# MainBoard.net
KiCad netlist of a schematic drawn in Altium Designer
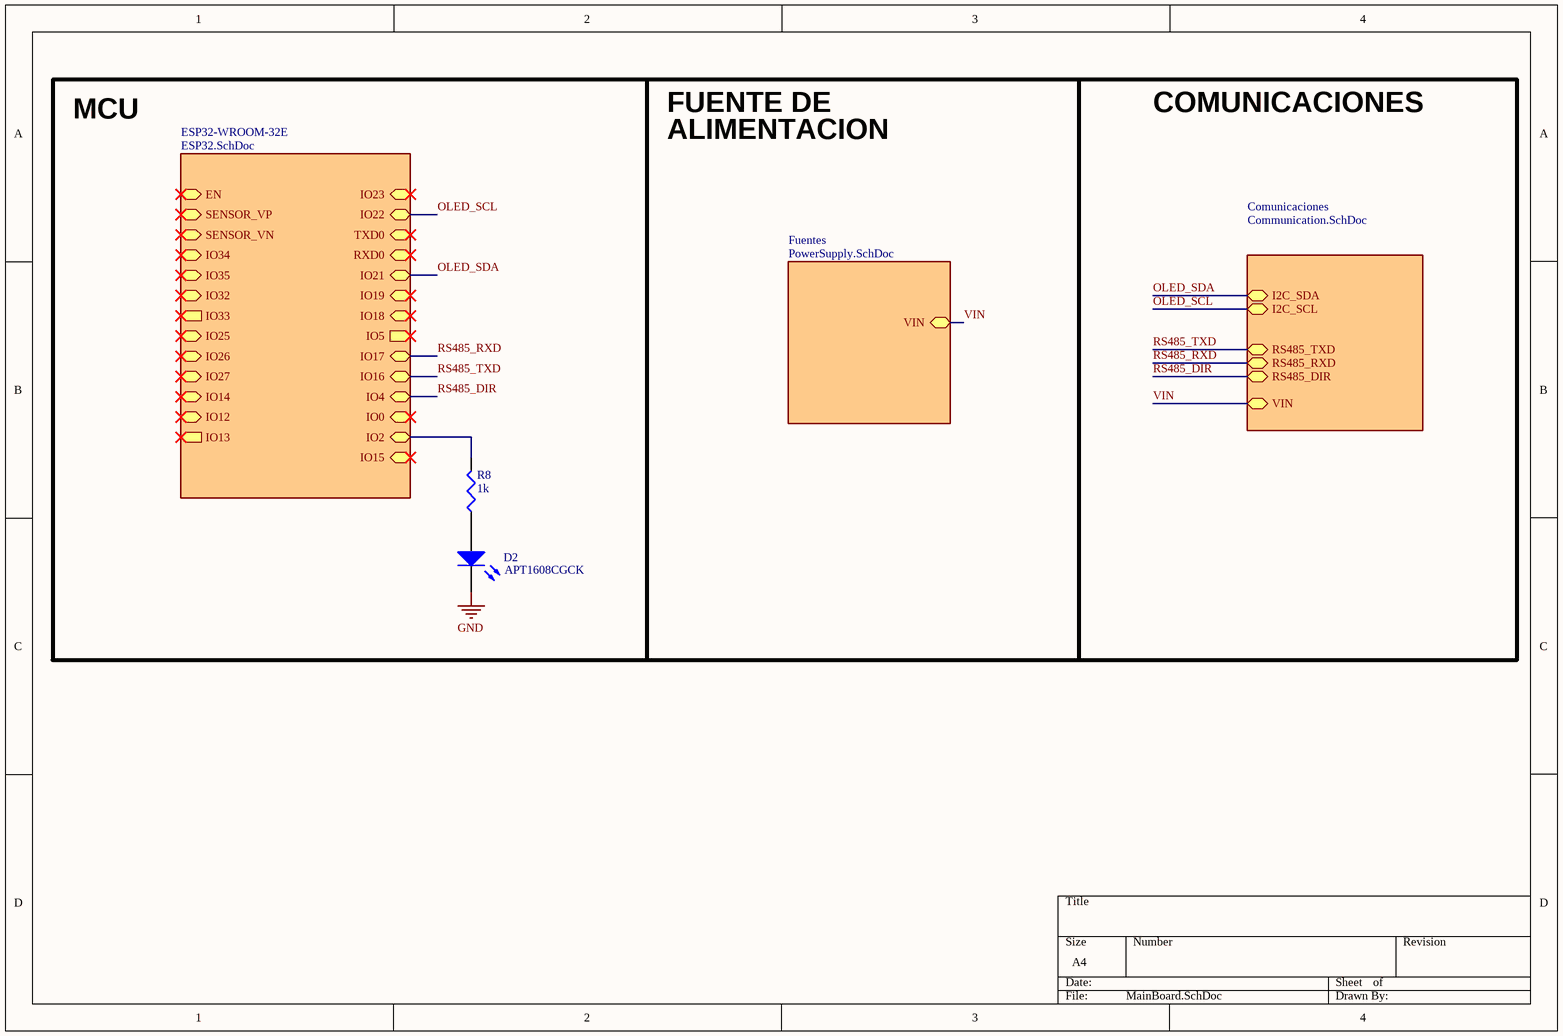
[diagram p0: MainBoard.SchDoc]

(export (version "E")
  (design (tool "Eeschema 10.0.6"))
  (components
    (comp (ref "D2")
      (value "APT1608CGCK")
      (footprint "ChipDiode1608")
      (description "LED 1.6x0.8 mm 570 nm GRN CLR SMD")
      (fields (field (name "PUBLISHER") "Altium Limited"))
      (libsource (lib "Miscellaneous Devices") (part "LED2"))
    )
    (comp (ref "R8")
      (value "1k")
      (footprint "RESC2012N")
      (description "Resistor")
      (fields (field (name "PUBLISHER") "Altium Limited"))
      (libsource (lib "Miscellaneous Devices") (part "Res3"))
    )
  )
  (nets
    (net (code "3") (name "/IO2") (class "Default")
      (node (ref "R8") (pin "2") (pinfunction "2_2") (pintype "passive"))
    )
    (net (code "29") (name "GND") (class "Default")
      (node (ref "D2") (pin "2") (pinfunction "K_2") (pintype "passive"))
    )
    (net (code "30") (name "Net-(D2-A)") (class "Default")
      (node (ref "D2") (pin "1") (pinfunction "A_1") (pintype "passive"))
      (node (ref "R8") (pin "1") (pinfunction "1_1") (pintype "passive"))
    )
  )
)
